# Digital_Inputs_24V.net
KiCad netlist of a schematic drawn in Altium Designer
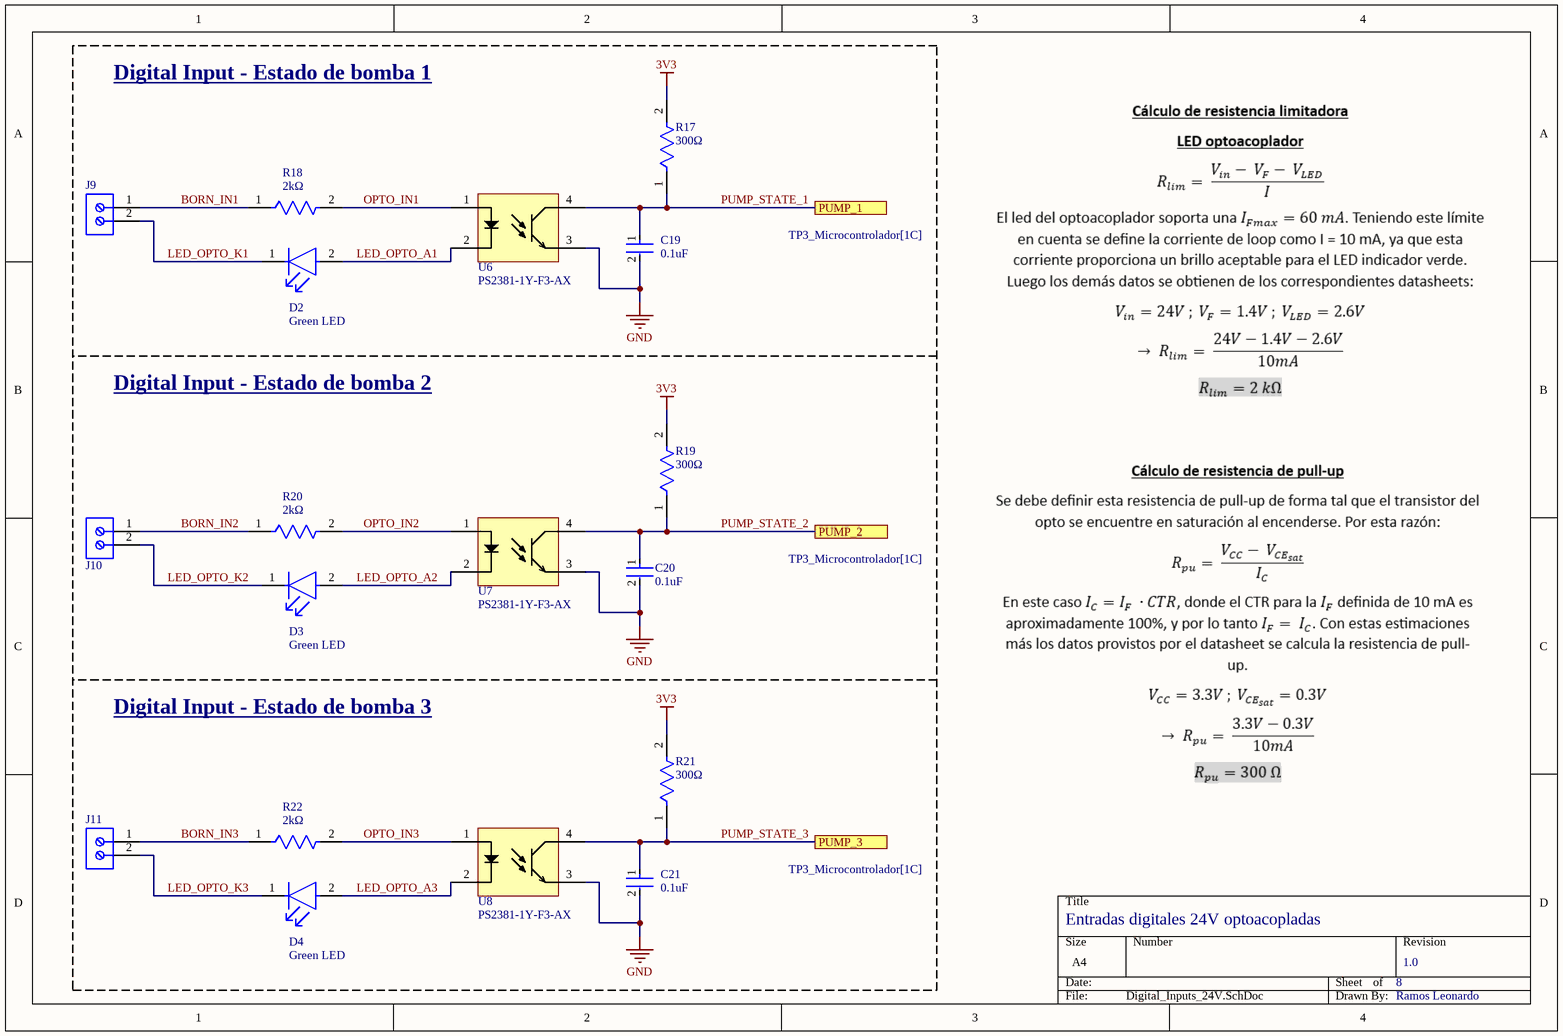
[diagram p0: Digital_Inputs_24V.SchDoc]

(export (version "E")
  (design (tool "Eeschema 10.0.6"))
  (components
    (comp (ref "C19")
      (value "0.1uF")
      (footprint "FP-CC0805-0_85-MFG")
      (description "CAP CER 0.1UF 25V X7R 0805")
      (fields (field (name "MANUFACTURER PART NUMBER") "CC0805KRX7R8BB104") (field (name "TOLERANCE") "0.1"))
      (libsource (lib "Altium Content Vault") (part "11868f565c42a9108669ba33697ecf6"))
    )
    (comp (ref "C20")
      (value "0.1uF")
      (footprint "FP-CC0805-0_85-MFG")
      (description "CAP CER 0.1UF 25V X7R 0805")
      (fields (field (name "MANUFACTURER PART NUMBER") "CC0805KRX7R8BB104") (field (name "TOLERANCE") "0.1"))
      (libsource (lib "Altium Content Vault") (part "11868f565c42a9108669ba33697ecf6"))
    )
    (comp (ref "C21")
      (value "0.1uF")
      (footprint "FP-CC0805-0_85-MFG")
      (description "CAP CER 0.1UF 25V X7R 0805")
      (fields (field (name "MANUFACTURER PART NUMBER") "CC0805KRX7R8BB104") (field (name "TOLERANCE") "0.1"))
      (libsource (lib "Altium Content Vault") (part "11868f565c42a9108669ba33697ecf6"))
    )
    (comp (ref "D2")
      (value "Green LED")
      (footprint "FP-LTST-C170GKT-MFG")
      (description "LED GREEN CLEAR SMD LTST-C170GKT")
      (fields (field (name "VOLTAGE") "5V"))
      (libsource (lib "Altium Content Vault") (part "8706943c75ba83719d021d2fdc84c58"))
    )
    (comp (ref "D3")
      (value "Green LED")
      (footprint "FP-LTST-C170GKT-MFG")
      (description "LED GREEN CLEAR SMD LTST-C170GKT")
      (fields (field (name "VOLTAGE") "5V"))
      (libsource (lib "Altium Content Vault") (part "8706943c75ba83719d021d2fdc84c58"))
    )
    (comp (ref "D4")
      (value "Green LED")
      (footprint "FP-LTST-C170GKT-MFG")
      (description "LED GREEN CLEAR SMD LTST-C170GKT")
      (fields (field (name "VOLTAGE") "5V"))
      (libsource (lib "Altium Content Vault") (part "8706943c75ba83719d021d2fdc84c58"))
    )
    (comp (ref "J9")
      (value "691137710002")
      (footprint "691137710002")
      (libsource (lib "Altium Content Vault") (part "TBL - 1R - 02P - Screw"))
    )
    (comp (ref "J10")
      (value "691137710002")
      (footprint "691137710002")
      (libsource (lib "Altium Content Vault") (part "TBL - 1R - 02P - Screw"))
    )
    (comp (ref "J11")
      (value "691137710002")
      (footprint "691137710002")
      (libsource (lib "Altium Content Vault") (part "TBL - 1R - 02P - Screw"))
    )
    (comp (ref "R17")
      (value "CRCW08054K70JNEA")
      (footprint "FP-CRCW0805-e3-IPC_B")
      (description "RES Thick Film, 5%, 0.125W, 200ppm/°C, 0805")
      (fields (field (name "TOLERANCE") "5%") (field (name "RESISTANCE") "300Ω"))
      (libsource (lib "Altium Content Vault") (part "1029c3af85768c4190bb7ad29bc67b5"))
    )
    (comp (ref "R18")
      (value "CRCW08054K70JNEA")
      (footprint "FP-CRCW0805-e3-IPC_B")
      (description "RES Thick Film, 5%, 0.125W, 200ppm/°C, 0805")
      (fields (field (name "TOLERANCE") "5%") (field (name "RESISTANCE") "2kΩ"))
      (libsource (lib "Altium Content Vault") (part "1029c3af85768c4190bb7ad29bc67b5"))
    )
    (comp (ref "R19")
      (value "CRCW08054K70JNEA")
      (footprint "FP-CRCW0805-e3-IPC_B")
      (description "RES Thick Film, 5%, 0.125W, 200ppm/°C, 0805")
      (fields (field (name "TOLERANCE") "5%") (field (name "RESISTANCE") "300Ω"))
      (libsource (lib "Altium Content Vault") (part "1029c3af85768c4190bb7ad29bc67b5"))
    )
    (comp (ref "R20")
      (value "CRCW08054K70JNEA")
      (footprint "FP-CRCW0805-e3-IPC_B")
      (description "RES Thick Film, 4.7kΩ, 5%, 0.125W, 200ppm/°C, 0805")
      (fields (field (name "TOLERANCE") "5%") (field (name "RESISTANCE") "2kΩ"))
      (libsource (lib "Altium Content Vault") (part "1029c3af85768c4190bb7ad29bc67b5"))
    )
    (comp (ref "R21")
      (value "CRCW08054K70JNEA")
      (footprint "FP-CRCW0805-e3-IPC_B")
      (description "RES Thick Film, 5%, 0.125W, 200ppm/°C, 0805")
      (fields (field (name "TOLERANCE") "5%") (field (name "RESISTANCE") "300Ω"))
      (libsource (lib "Altium Content Vault") (part "1029c3af85768c4190bb7ad29bc67b5"))
    )
    (comp (ref "R22")
      (value "CRCW08054K70JNEA")
      (footprint "FP-CRCW0805-e3-IPC_B")
      (description "RES Thick Film, 4.7kΩ, 5%, 0.125W, 200ppm/°C, 0805")
      (fields (field (name "TOLERANCE") "5%") (field (name "RESISTANCE") "2kΩ"))
      (libsource (lib "Altium Content Vault") (part "1029c3af85768c4190bb7ad29bc67b5"))
    )
    (comp (ref "U6")
      (value "PS2381-1Y-F3-AX")
      (footprint "LSOP254P1020X230-4N")
      (description "PS2381-1Y-F3-AX Optocoupler, Transistor, 5Kv, Lsop-4 Rohs Compliant: Yes")
      (libsource (lib "Altium Content Vault") (part "PS2381-1Y-F3-AX"))
    )
    (comp (ref "U7")
      (value "PS2381-1Y-F3-AX")
      (footprint "LSOP254P1020X230-4N")
      (description "PS2381-1Y-F3-AX Optocoupler, Transistor, 5Kv, Lsop-4 Rohs Compliant: Yes")
      (libsource (lib "Altium Content Vault") (part "PS2381-1Y-F3-AX"))
    )
    (comp (ref "U8")
      (value "PS2381-1Y-F3-AX")
      (footprint "LSOP254P1020X230-4N")
      (description "PS2381-1Y-F3-AX Optocoupler, Transistor, 5Kv, Lsop-4 Rohs Compliant: Yes")
      (libsource (lib "Altium Content Vault") (part "PS2381-1Y-F3-AX"))
    )
  )
  (nets
    (net (code "1") (name "/BORN_IN1") (class "Default")
      (node (ref "J9") (pin "1") (pinfunction "1_1") (pintype "passive"))
      (node (ref "R18") (pin "1") (pinfunction "1_1") (pintype "passive"))
    )
    (net (code "2") (name "/BORN_IN2") (class "Default")
      (node (ref "J10") (pin "1") (pinfunction "1_1") (pintype "passive"))
      (node (ref "R20") (pin "1") (pinfunction "1_1") (pintype "passive"))
    )
    (net (code "3") (name "/BORN_IN3") (class "Default")
      (node (ref "J11") (pin "1") (pinfunction "1_1") (pintype "passive"))
      (node (ref "R22") (pin "1") (pinfunction "1_1") (pintype "passive"))
    )
    (net (code "4") (name "/LED_OPTO_A1") (class "Default")
      (node (ref "D2") (pin "2") (pinfunction "A_2") (pintype "passive"))
      (node (ref "U6") (pin "2") (pinfunction "Cathode_2") (pintype "passive"))
    )
    (net (code "5") (name "/LED_OPTO_A2") (class "Default")
      (node (ref "D3") (pin "2") (pinfunction "A_2") (pintype "passive"))
      (node (ref "U7") (pin "2") (pinfunction "Cathode_2") (pintype "passive"))
    )
    (net (code "6") (name "/LED_OPTO_A3") (class "Default")
      (node (ref "D4") (pin "2") (pinfunction "A_2") (pintype "passive"))
      (node (ref "U8") (pin "2") (pinfunction "Cathode_2") (pintype "passive"))
    )
    (net (code "7") (name "/LED_OPTO_K1") (class "Default")
      (node (ref "D2") (pin "1") (pinfunction "C_1") (pintype "passive"))
      (node (ref "J9") (pin "2") (pinfunction "2_2") (pintype "passive"))
    )
    (net (code "8") (name "/LED_OPTO_K2") (class "Default")
      (node (ref "D3") (pin "1") (pinfunction "C_1") (pintype "passive"))
      (node (ref "J10") (pin "2") (pinfunction "2_2") (pintype "passive"))
    )
    (net (code "9") (name "/LED_OPTO_K3") (class "Default")
      (node (ref "D4") (pin "1") (pinfunction "C_1") (pintype "passive"))
      (node (ref "J11") (pin "2") (pinfunction "2_2") (pintype "passive"))
    )
    (net (code "10") (name "/OPTO_IN1") (class "Default")
      (node (ref "R18") (pin "2") (pinfunction "2_2") (pintype "passive"))
      (node (ref "U6") (pin "1") (pinfunction "Anode_1") (pintype "passive"))
    )
    (net (code "11") (name "/OPTO_IN2") (class "Default")
      (node (ref "R20") (pin "2") (pinfunction "2_2") (pintype "passive"))
      (node (ref "U7") (pin "1") (pinfunction "Anode_1") (pintype "passive"))
    )
    (net (code "12") (name "/OPTO_IN3") (class "Default")
      (node (ref "R22") (pin "2") (pinfunction "2_2") (pintype "passive"))
      (node (ref "U8") (pin "1") (pinfunction "Anode_1") (pintype "passive"))
    )
    (net (code "13") (name "/PUMP_STATE_1") (class "Default")
      (node (ref "C19") (pin "1") (pinfunction "1_1") (pintype "passive"))
      (node (ref "R17") (pin "1") (pinfunction "1_1") (pintype "passive"))
      (node (ref "U6") (pin "4") (pinfunction "Collector_4") (pintype "power_in"))
    )
    (net (code "14") (name "/PUMP_STATE_2") (class "Default")
      (node (ref "C20") (pin "1") (pinfunction "1_1") (pintype "passive"))
      (node (ref "R19") (pin "1") (pinfunction "1_1") (pintype "passive"))
      (node (ref "U7") (pin "4") (pinfunction "Collector_4") (pintype "power_in"))
    )
    (net (code "15") (name "/PUMP_STATE_3") (class "Default")
      (node (ref "C21") (pin "1") (pinfunction "1_1") (pintype "passive"))
      (node (ref "R21") (pin "1") (pinfunction "1_1") (pintype "passive"))
      (node (ref "U8") (pin "4") (pinfunction "Collector_4") (pintype "power_in"))
    )
    (net (code "16") (name "3V3") (class "Default")
      (node (ref "R17") (pin "2") (pinfunction "2_2") (pintype "passive"))
      (node (ref "R19") (pin "2") (pinfunction "2_2") (pintype "passive"))
      (node (ref "R21") (pin "2") (pinfunction "2_2") (pintype "passive"))
    )
    (net (code "17") (name "GND") (class "Default")
      (node (ref "C19") (pin "2") (pinfunction "2_2") (pintype "passive"))
      (node (ref "C20") (pin "2") (pinfunction "2_2") (pintype "passive"))
      (node (ref "C21") (pin "2") (pinfunction "2_2") (pintype "passive"))
      (node (ref "U6") (pin "3") (pinfunction "Emitter_3") (pintype "power_in"))
      (node (ref "U7") (pin "3") (pinfunction "Emitter_3") (pintype "power_in"))
      (node (ref "U8") (pin "3") (pinfunction "Emitter_3") (pintype "power_in"))
    )
  )
)
